# filtro.net
KiCad netlist of a schematic drawn in Altium Designer
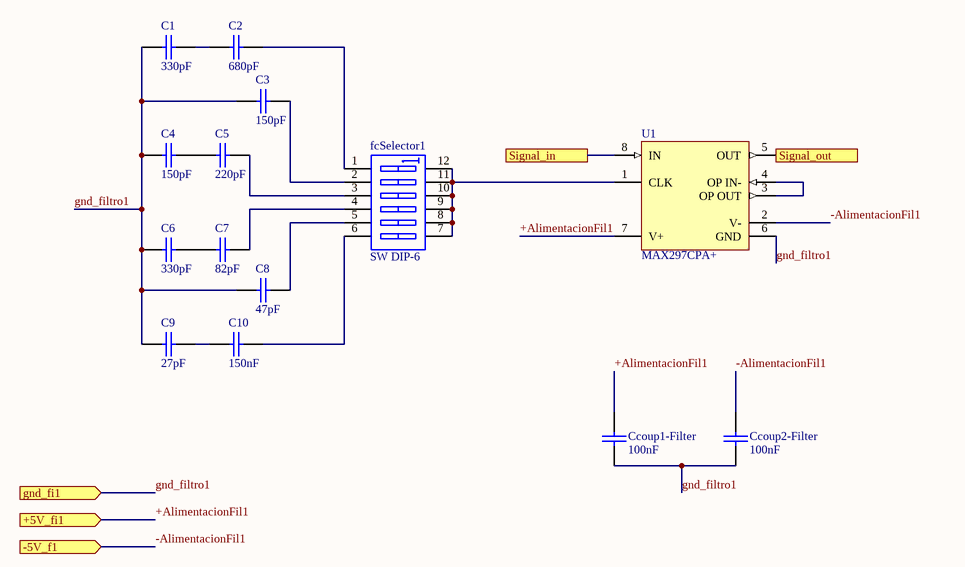
[diagram p0: filtro.SchDoc]

(export (version "E")
  (design (tool "Eeschema 10.0.6"))
  (components
    (comp (ref "C1") (value "330pF") (footprint "CAP200") (libsource (lib "LIBEBAL") (part "CAP")))
    (comp (ref "C2") (value "680pF") (footprint "CAP200") (libsource (lib "LIBEBAL") (part "CAP")))
    (comp (ref "C3") (value "150pF") (footprint "CAP200") (libsource (lib "LIBEBAL") (part "CAP")))
    (comp (ref "C4") (value "150pF") (footprint "CAP200") (libsource (lib "LIBEBAL") (part "CAP")))
    (comp (ref "C5") (value "220pF") (footprint "CAP200") (libsource (lib "LIBEBAL") (part "CAP")))
    (comp (ref "C6") (value "330pF") (footprint "CAP200") (libsource (lib "LIBEBAL") (part "CAP")))
    (comp (ref "C7") (value "82pF") (footprint "CAP200") (libsource (lib "LIBEBAL") (part "CAP")))
    (comp (ref "C8") (value "47pF") (footprint "CAP200") (libsource (lib "LIBEBAL") (part "CAP")))
    (comp (ref "C9") (value "27pF") (footprint "CAP200") (libsource (lib "LIBEBAL") (part "CAP")))
    (comp (ref "C10") (value "150nF") (footprint "CAP200") (libsource (lib "LIBEBAL") (part "CAP")))
    (comp (ref "Ccoup1-Filter") (value "100nF") (footprint "CAP200") (libsource (lib "LIBEBAL") (part "CAP")))
    (comp (ref "Ccoup2-Filter") (value "100nF") (footprint "CAP200") (libsource (lib "LIBEBAL") (part "CAP")))
    (comp (ref "fcSelector1")
      (value "SW DIP-6")
      (footprint "DIP-12/SW")
      (description "DIP Switch, 6 Position, SPST")
      (fields (field (name "PUBLISHER") "Altium Limited"))
      (libsource (lib "Miscellaneous Devices") (part "SW DIP-6"))
    )
    (comp (ref "U1")
      (value "MAX297CPA+")
      (footprint "MAXM-P8+2")
      (fields (field (name "GENERIC PART NUMBER") "MAX297"))
      (libsource (lib "Maxim Analog Filters") (part "MAX297CPA+"))
    )
  )
  (nets
    (net (code "1") (name "/+AlimentacionFil1") (class "Default")
      (node (ref "Ccoup1-Filter") (pin "2") (pinfunction "2_2") (pintype "passive"))
      (node (ref "U1") (pin "7") (pinfunction "V+_7") (pintype "power_in"))
    )
    (net (code "2") (name "/-AlimentacionFil1") (class "Default")
      (node (ref "Ccoup2-Filter") (pin "2") (pinfunction "2_2") (pintype "passive"))
      (node (ref "U1") (pin "2") (pinfunction "V-_2") (pintype "power_in"))
    )
    (net (code "3") (name "/Signal_in") (class "Default")
      (node (ref "U1") (pin "8") (pinfunction "IN_8") (pintype "input"))
    )
    (net (code "4") (name "/Signal_out") (class "Default")
      (node (ref "U1") (pin "5") (pinfunction "OUT_5") (pintype "output"))
    )
    (net (code "5") (name "/gnd_filtro1") (class "Default")
      (node (ref "C1") (pin "1") (pinfunction "1_1") (pintype "passive"))
      (node (ref "C3") (pin "1") (pinfunction "1_1") (pintype "passive"))
      (node (ref "C4") (pin "1") (pinfunction "1_1") (pintype "passive"))
      (node (ref "C6") (pin "1") (pinfunction "1_1") (pintype "passive"))
      (node (ref "C8") (pin "1") (pinfunction "1_1") (pintype "passive"))
      (node (ref "C9") (pin "1") (pinfunction "1_1") (pintype "passive"))
      (node (ref "Ccoup1-Filter") (pin "1") (pinfunction "1_1") (pintype "passive"))
      (node (ref "Ccoup2-Filter") (pin "1") (pinfunction "1_1") (pintype "passive"))
      (node (ref "U1") (pin "6") (pinfunction "GND_6") (pintype "power_in"))
    )
    (net (code "6") (name "Net-(C1-Pad2)") (class "Default")
      (node (ref "C1") (pin "2") (pinfunction "2_2") (pintype "passive"))
      (node (ref "C2") (pin "1") (pinfunction "1_1") (pintype "passive"))
    )
    (net (code "7") (name "Net-(C4-Pad2)") (class "Default")
      (node (ref "C4") (pin "2") (pinfunction "2_2") (pintype "passive"))
      (node (ref "C5") (pin "1") (pinfunction "1_1") (pintype "passive"))
    )
    (net (code "8") (name "Net-(C6-Pad2)") (class "Default")
      (node (ref "C6") (pin "2") (pinfunction "2_2") (pintype "passive"))
      (node (ref "C7") (pin "1") (pinfunction "1_1") (pintype "passive"))
    )
    (net (code "9") (name "Net-(C10-Pad1)") (class "Default")
      (node (ref "C10") (pin "1") (pinfunction "1_1") (pintype "passive"))
      (node (ref "C9") (pin "2") (pinfunction "2_2") (pintype "passive"))
    )
    (net (code "10") (name "Net-(U1-CLK)") (class "Default")
      (node (ref "U1") (pin "1") (pinfunction "CLK_1") (pintype "passive"))
      (node (ref "fcSelector1") (pin "10") (pinfunction "B3_10") (pintype "passive"))
      (node (ref "fcSelector1") (pin "11") (pinfunction "B2_11") (pintype "passive"))
      (node (ref "fcSelector1") (pin "12") (pinfunction "B1_12") (pintype "passive"))
      (node (ref "fcSelector1") (pin "7") (pinfunction "B6_7") (pintype "passive"))
      (node (ref "fcSelector1") (pin "8") (pinfunction "B5_8") (pintype "passive"))
      (node (ref "fcSelector1") (pin "9") (pinfunction "B4_9") (pintype "passive"))
    )
    (net (code "11") (name "Net-(U1-OP_IN-)") (class "Default")
      (node (ref "U1") (pin "3") (pinfunction "OP_OUT_3") (pintype "output"))
      (node (ref "U1") (pin "4") (pinfunction "OP_IN-_4") (pintype "input"))
    )
    (net (code "12") (name "Net-(fcSelector1-A1)") (class "Default")
      (node (ref "C2") (pin "2") (pinfunction "2_2") (pintype "passive"))
      (node (ref "fcSelector1") (pin "1") (pinfunction "A1_1") (pintype "passive"))
    )
    (net (code "13") (name "Net-(fcSelector1-A2)") (class "Default")
      (node (ref "C3") (pin "2") (pinfunction "2_2") (pintype "passive"))
      (node (ref "fcSelector1") (pin "2") (pinfunction "A2_2") (pintype "passive"))
    )
    (net (code "14") (name "Net-(fcSelector1-A3)") (class "Default")
      (node (ref "C5") (pin "2") (pinfunction "2_2") (pintype "passive"))
      (node (ref "fcSelector1") (pin "3") (pinfunction "A3_3") (pintype "passive"))
    )
    (net (code "15") (name "Net-(fcSelector1-A4)") (class "Default")
      (node (ref "C7") (pin "2") (pinfunction "2_2") (pintype "passive"))
      (node (ref "fcSelector1") (pin "4") (pinfunction "A4_4") (pintype "passive"))
    )
    (net (code "16") (name "Net-(fcSelector1-A5)") (class "Default")
      (node (ref "C8") (pin "2") (pinfunction "2_2") (pintype "passive"))
      (node (ref "fcSelector1") (pin "5") (pinfunction "A5_5") (pintype "passive"))
    )
    (net (code "17") (name "Net-(fcSelector1-A6)") (class "Default")
      (node (ref "C10") (pin "2") (pinfunction "2_2") (pintype "passive"))
      (node (ref "fcSelector1") (pin "6") (pinfunction "A6_6") (pintype "passive"))
    )
  )
)
